# NuPrism_MCPMT_-_ADA4945-1_and_Filter_-_R.net
KiCad netlist of a schematic drawn in Altium Designer
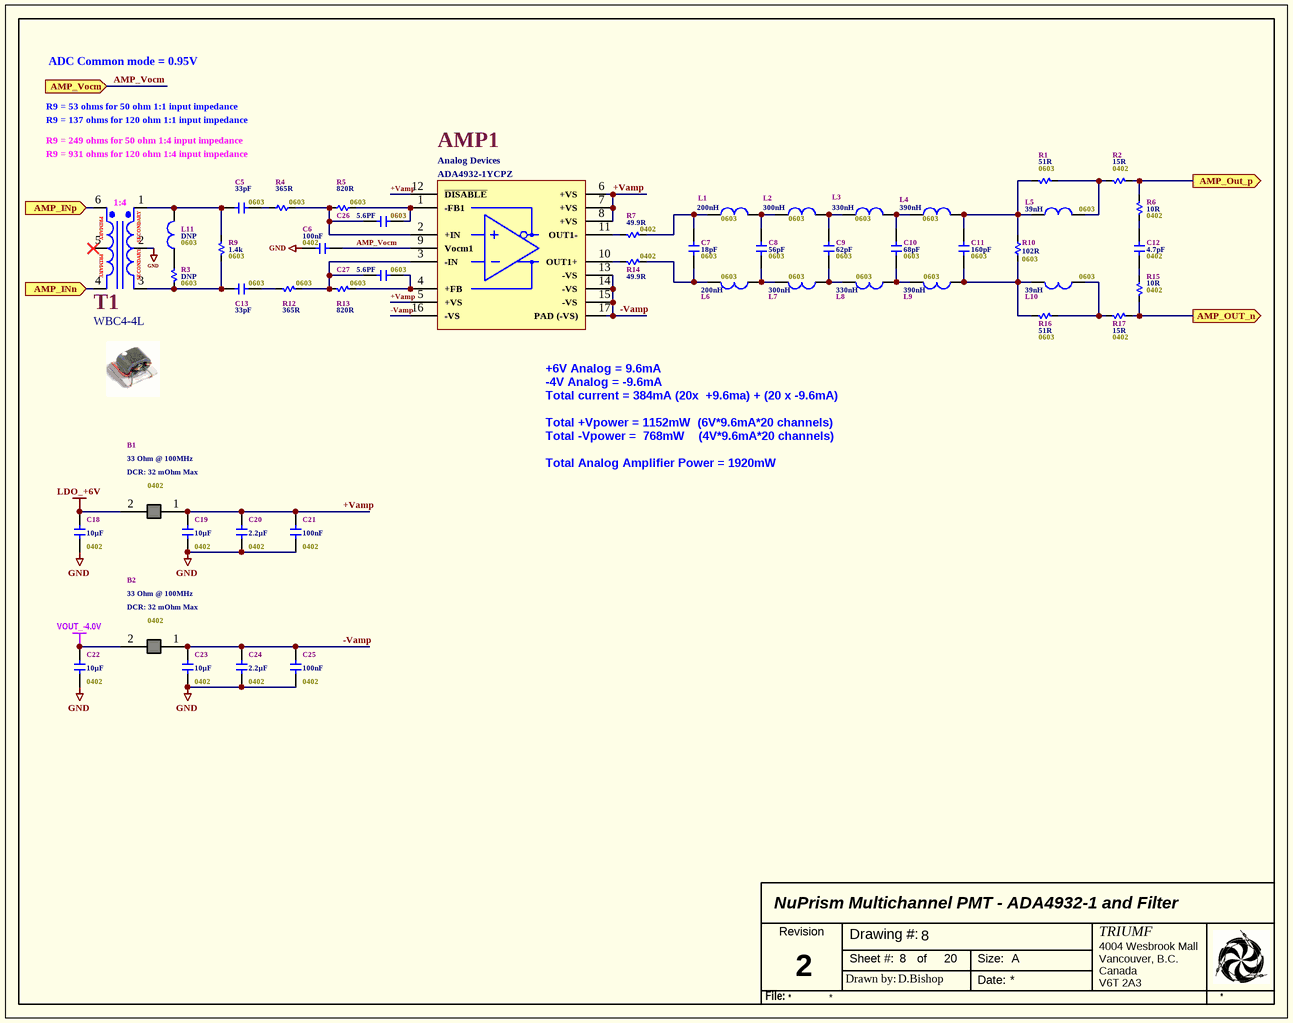
[diagram p0: NuPrism_MCPMT - ADA4945-1 and Filter - Rev2.SchDoc]

(export (version "E")
  (design (tool "Eeschema 10.0.6"))
  (components
    (comp (ref "AMP1")
      (value "ADA4932-1YCPZ")
      (footprint "QFN50P300X300X100-16N_ALT")
      (description "High Speed, ±0.1 µV/˚C Offset Drift, Fully Differential ADC Driver")
      (fields (field (name "MANUFACTURER") "Analog Devices") (field (name "PARTNO") "ADA4932-1YCPZ"))
      (libsource (lib "NuPrism_MCPMT") (part "ADA4932-1YCPZ_ALT"))
    )
    (comp (ref "B1")
      (value "BLM15PX600SN1D")
      (footprint "0402")
      (description "60 Ohms @ 100MHz Ferrite Bead 0402 2.5A")
      (fields
        (field (name "MANUFACTURER") "Murata")
        (field (name "DCR") "32 mOhm Max")
        (field (name "IMPEDANCE @ FREQUENCY") "33 Ohm @ 100MHz")
        (field (name "PACKAGE") "0402")
      )
      (libsource (lib "Clock Distribution Module") (part "Ferrite Bead"))
    )
    (comp (ref "B2")
      (value "BLM15PX600SN1D")
      (footprint "0402")
      (description "60 Ohms @ 100MHz Ferrite Bead 0402 2.5A")
      (fields
        (field (name "MANUFACTURER") "Murata")
        (field (name "DCR") "32 mOhm Max")
        (field (name "IMPEDANCE @ FREQUENCY") "33 Ohm @ 100MHz")
        (field (name "PACKAGE") "0402")
      )
      (libsource (lib "Clock Distribution Module") (part "Ferrite Bead"))
    )
    (comp (ref "C5")
      (value "C0603C330J1GAC7867")
      (footprint "0603")
      (description "33 pF ±5% 100V Ceramic Capacitor C0G, NP0 0603")
      (fields
        (field (name "MANUFACTURER") "KEMET")
        (field (name "CAPACITANCE") "33pF")
        (field (name "PACKAGE") "0603")
        (field (name "VOLTAGE") "100V")
      )
      (libsource (lib "altium-import") (part "root_1_CAP-SMALL_"))
    )
    (comp (ref "C6")
      (value "C0402C104K4RACTU")
      (footprint "0402")
      (description "SMD/SMT 0402 16V 0.1uF X7R 10%")
      (fields
        (field (name "MANUFACTURER") "Kemet")
        (field (name "CAPACITANCE") "100nF")
        (field (name "PACKAGE") "0402")
        (field (name "VOLTAGE") "16V")
      )
      (libsource (lib "NuPrism_MCPMT") (part "CAP-SMALL"))
    )
    (comp (ref "C7")
      (value "CC0603JPNPO9BN180")
      (footprint "0603")
      (description "18 pF ±5% 50V Ceramic Capacitor C0G, NP0 0603")
      (fields
        (field (name "CAPACITANCE") "18pF")
        (field (name "PACKAGE") "0603")
        (field (name "MANUFACTURER") "Yageo")
        (field (name "VOLTAGE") "50V")
      )
      (libsource (lib "altium-import") (part "root_2_CAP-SMALL_"))
    )
    (comp (ref "C8")
      (value "C0603C560J5GAC7867")
      (footprint "0603")
      (description "56 pF ±5% 50V Ceramic Capacitor C0G, NP0 0603 (1608 Metric)")
      (fields
        (field (name "MANUFACTURER") "KEMET")
        (field (name "CAPACITANCE") "56pF")
        (field (name "PACKAGE") "0603")
        (field (name "VOLTAGE") "50V")
      )
      (libsource (lib "altium-import") (part "root_2_CAP-SMALL_"))
    )
    (comp (ref "C9")
      (value "CC0603JRNPO9BN620")
      (footprint "0603")
      (description "62 pF ±5% 50V Ceramic Capacitor C0G, NP0 0603 (1608 Metric)")
      (fields
        (field (name "MANUFACTURER") "YAGEO")
        (field (name "CAPACITANCE") "62pF")
        (field (name "PACKAGE") "0603")
        (field (name "VOLTAGE") "50V")
      )
      (libsource (lib "altium-import") (part "root_2_CAP-SMALL_"))
    )
    (comp (ref "C10")
      (value "CC0603JRNPO9BN680")
      (footprint "0603")
      (description "CAP CER 68PF 50V C0G/NPO 0603 (1608 Metric)")
      (fields
        (field (name "CAPACITANCE") "68pF")
        (field (name "PACKAGE") "0603")
        (field (name "MANUFACTURER") "Yageo")
        (field (name "VOLTAGE") "50V")
      )
      (libsource (lib "altium-import") (part "root_2_CAP-SMALL_"))
    )
    (comp (ref "C11")
      (value "CC0603JRNPO9BN161")
      (footprint "0603")
      (description "160 pF ±5% 50V Ceramic Capacitor C0G, NP0 0603 (1608 Metric)")
      (fields
        (field (name "MANUFACTURER") "YAGEO")
        (field (name "CAPACITANCE") "160pF")
        (field (name "PACKAGE") "0603")
        (field (name "VOLTAGE") "50V")
      )
      (libsource (lib "altium-import") (part "root_2_CAP-SMALL_"))
    )
    (comp (ref "C12")
      (value "CC0402BRNPO9BN4R7")
      (footprint "0402")
      (description "4.7pF ±0.1pF 50V Ceramic Capacitor C0G, NP0 0402")
      (fields
        (field (name "MANUFACTURER") "Yageo")
        (field (name "CAPACITANCE") "4.7pF")
        (field (name "PACKAGE") "0402")
        (field (name "VOLTAGE") "50V")
      )
      (libsource (lib "altium-import") (part "root_2_CAP-SMALL_"))
    )
    (comp (ref "C13")
      (value "C0603C330J1GAC7867")
      (footprint "0603")
      (description "33 pF ±5% 100V Ceramic Capacitor C0G, NP0 0603")
      (fields
        (field (name "MANUFACTURER") "KEMET")
        (field (name "CAPACITANCE") "33pF")
        (field (name "PACKAGE") "0603")
        (field (name "VOLTAGE") "100V")
      )
      (libsource (lib "altium-import") (part "root_3_mirrored_CAP-SMALL_"))
    )
    (comp (ref "C18")
      (value "CL05A106MQ5NRNC")
      (footprint "0402")
      (description "10 µF ±20% 6.3V Ceramic Capacitor X5R 0402 (1005 Metric)")
      (fields
        (field (name "CAPACITANCE") "10µF")
        (field (name "PACKAGE") "0402")
        (field (name "MANUFACTURER") "Samsung Electro-Mechanics")
        (field (name "VOLTAGE") "6.3V")
      )
      (libsource (lib "") (part "root_2_CAP-SMALL__1"))
    )
    (comp (ref "C19")
      (value "CL05A106MQ5NRNC")
      (footprint "0402")
      (description "10 µF ±20% 6.3V Ceramic Capacitor X5R 0402 (1005 Metric)")
      (fields
        (field (name "CAPACITANCE") "10µF")
        (field (name "PACKAGE") "0402")
        (field (name "MANUFACTURER") "Samsung Electro-Mechanics")
        (field (name "VOLTAGE") "6.3V")
      )
      (libsource (lib "") (part "root_2_CAP-SMALL__1"))
    )
    (comp (ref "C20")
      (value "TMK105CBJ225KV-F")
      (footprint "0402")
      (description "SMD/SMT 0402 25V 2.2uF 10% X5R")
      (fields
        (field (name "MANUFACTURER") "Taiyo Yuden")
        (field (name "CAPACITANCE") "2.2µF")
        (field (name "PACKAGE") "0402")
        (field (name "VOLTAGE") "25V")
      )
      (libsource (lib "altium-import") (part "root_0_CAP-SMALL_"))
    )
    (comp (ref "C21")
      (value "C0402C104K4RACTU")
      (footprint "0402")
      (description "SMD/SMT 0402 16V 0.1uF X7R 10%")
      (fields
        (field (name "MANUFACTURER") "Kemet")
        (field (name "CAPACITANCE") "100nF")
        (field (name "PACKAGE") "0402")
        (field (name "VOLTAGE") "16V")
      )
      (libsource (lib "NuPrism_MCPMT") (part "CAP-SMALL"))
    )
    (comp (ref "C22")
      (value "CL05A106MQ5NRNC")
      (footprint "0402")
      (description "10 µF ±20% 6.3V Ceramic Capacitor X5R 0402 (1005 Metric)")
      (fields
        (field (name "CAPACITANCE") "10µF")
        (field (name "PACKAGE") "0402")
        (field (name "MANUFACTURER") "Samsung Electro-Mechanics")
        (field (name "VOLTAGE") "6.3V")
      )
      (libsource (lib "") (part "root_2_CAP-SMALL__1"))
    )
    (comp (ref "C23")
      (value "CL05A106MQ5NRNC")
      (footprint "0402")
      (description "10 µF ±20% 6.3V Ceramic Capacitor X5R 0402 (1005 Metric)")
      (fields
        (field (name "CAPACITANCE") "10µF")
        (field (name "PACKAGE") "0402")
        (field (name "MANUFACTURER") "Samsung Electro-Mechanics")
        (field (name "VOLTAGE") "6.3V")
      )
      (libsource (lib "") (part "root_2_CAP-SMALL__1"))
    )
    (comp (ref "C24")
      (value "TMK105CBJ225KV-F")
      (footprint "0402")
      (description "SMD/SMT 0402 25V 2.2uF 10% X5R")
      (fields
        (field (name "MANUFACTURER") "Taiyo Yuden")
        (field (name "CAPACITANCE") "2.2µF")
        (field (name "PACKAGE") "0402")
        (field (name "VOLTAGE") "25V")
      )
      (libsource (lib "altium-import") (part "root_0_CAP-SMALL_"))
    )
    (comp (ref "C25")
      (value "C0402C104K4RACTU")
      (footprint "0402")
      (description "SMD/SMT 0402 16V 0.1uF X7R 10%")
      (fields
        (field (name "MANUFACTURER") "Kemet")
        (field (name "CAPACITANCE") "100nF")
        (field (name "PACKAGE") "0402")
        (field (name "VOLTAGE") "16V")
      )
      (libsource (lib "NuPrism_MCPMT") (part "CAP-SMALL"))
    )
    (comp (ref "C26")
      (value "06035A5R6JAT2A")
      (footprint "0603")
      (description "5.6 pF ±5% 50V Ceramic Capacitor C0G, NP0 0603")
      (fields
        (field (name "MANUFACTURER") "KYOCERA AVX")
        (field (name "CAPACITANCE") "5.6PF")
        (field (name "PACKAGE") "0603")
        (field (name "VOLTAGE") "50V")
      )
      (libsource (lib "altium-import") (part "root_3_CAP-SMALL_"))
    )
    (comp (ref "C27")
      (value "06035A5R6JAT2A")
      (footprint "0603")
      (description "5.6 pF ±5% 50V Ceramic Capacitor C0G, NP0 0603")
      (fields
        (field (name "MANUFACTURER") "KYOCERA AVX")
        (field (name "CAPACITANCE") "5.6PF")
        (field (name "PACKAGE") "0603")
        (field (name "VOLTAGE") "50V")
      )
      (libsource (lib "altium-import") (part "root_3_CAP-SMALL_"))
    )
    (comp (ref "L1")
      (value "LQW18ANR20J8ZD")
      (footprint "NumPrism Mutichannel PMT:0603 - Inductor")
      (description "200 nH Unshielded Wirewound Inductor 120 mA 2.40Ohm Max 0603")
      (fields
        (field (name "PACKAGE") "0603")
        (field (name "INDUCTANCE") "200nH")
        (field (name "MANUFACTURER") "Murata Electronics")
        (field (name "PARTNO") "LQW18ANR20G00D")
      )
      (libsource (lib "NuPrism - mPMT") (part "Inductor1"))
    )
    (comp (ref "L2")
      (value "LQW18ANR30G80D")
      (footprint "0603 - Inductor")
      (description "300 nH Unshielded Wirewound Inductor 220 mA 3.12Ohm Max 0603")
      (fields
        (field (name "PACKAGE") "0603")
        (field (name "INDUCTANCE") "300nH")
        (field (name "MANUFACTURER") "Coilcraft")
        (field (name "PARTNO") "LQW18ANR30G8ZD")
      )
      (libsource (lib "NuPrism - mPMT") (part "Inductor1"))
    )
    (comp (ref "L3")
      (value "LQW18CNR33J00D")
      (footprint "0603 - Inductor")
      (description "330 nH Unshielded Drum Core, Wirewound Inductor 630 mA 250mOhm Max 0603")
      (fields
        (field (name "PACKAGE") "0603")
        (field (name "INDUCTANCE") "330nH")
        (field (name "MANUFACTURER") "Murata Electronics")
      )
      (libsource (lib "NuPrism - mPMT") (part "Inductor1"))
    )
    (comp (ref "L4")
      (value "MLJ1608WR39JT000")
      (footprint "0603 - inductor")
      (description "390 nH Shielded Multilayer Inductor 450 mA 364mOhm Max 0603 (1608 Metric)")
      (fields
        (field (name "PACKAGE") "0603")
        (field (name "INDUCTANCE") "390nH")
        (field (name "MANUFACTURER") "TDK Corporation")
      )
      (libsource (lib "NuPrism - mPMT") (part "Inductor1"))
    )
    (comp (ref "L5")
      (value "LQW18AN39NJ00D")
      (footprint "0603 - Inductor_2")
      (description "39 nH Unshielded Wirewound Inductor 400 mA 260mOhm Max 0603 (1608 Metric)")
      (fields
        (field (name "PACKAGE") "0603")
        (field (name "INDUCTANCE") "39nH")
        (field (name "MANUFACTURER") "Murata Electronics")
      )
      (libsource (lib "NuPrism - mPMT") (part "Inductor1"))
    )
    (comp (ref "L6")
      (value "LQW18ANR20J8ZD")
      (footprint "0603 - Inductor")
      (description "200 nH Unshielded Wirewound Inductor 120 mA 2.40Ohm Max 0603")
      (fields
        (field (name "PACKAGE") "0603")
        (field (name "INDUCTANCE") "200nH")
        (field (name "MANUFACTURER") "Murata Electronics")
        (field (name "PARTNO") "LQW18ANR20G00D")
      )
      (libsource (lib "") (part "Inductor1_1"))
    )
    (comp (ref "L7")
      (value "LQW18ANR30G80D")
      (footprint "0603 - Inductor")
      (description "300 nH Unshielded Wirewound Inductor 220 mA 3.12Ohm Max 0603")
      (fields
        (field (name "PACKAGE") "0603")
        (field (name "INDUCTANCE") "300nH")
        (field (name "MANUFACTURER") "Coilcraft")
        (field (name "PARTNO") "LQW18ANR30G8ZD")
      )
      (libsource (lib "") (part "Inductor1_1"))
    )
    (comp (ref "L8")
      (value "LQW18CNR33J00D")
      (footprint "0603 - Inductor")
      (description "330 nH Unshielded Drum Core, Wirewound Inductor 630 mA 250mOhm Max 0603")
      (fields
        (field (name "PACKAGE") "0603")
        (field (name "INDUCTANCE") "330nH")
        (field (name "MANUFACTURER") "Murata Electronics")
      )
      (libsource (lib "") (part "Inductor1_1"))
    )
    (comp (ref "L9")
      (value "MLJ1608WR39JT000")
      (footprint "0603 - inductor")
      (description "390 nH Shielded Multilayer Inductor 450 mA 364mOhm Max 0603 (1608 Metric)")
      (fields
        (field (name "PACKAGE") "0603")
        (field (name "INDUCTANCE") "390nH")
        (field (name "MANUFACTURER") "TDK Corporation")
      )
      (libsource (lib "") (part "Inductor1_1"))
    )
    (comp (ref "L10")
      (value "LQW18AN39NJ00D")
      (footprint "0603 - Inductor_2")
      (description "39 nH Unshielded Wirewound Inductor 400 mA 260mOhm Max 0603 (1608 Metric)")
      (fields
        (field (name "PACKAGE") "0603")
        (field (name "INDUCTANCE") "39nH")
        (field (name "MANUFACTURER") "Murata Electronics")
      )
      (libsource (lib "") (part "Inductor1_1"))
    )
    (comp (ref "L11")
      (value "~")
      (footprint "0603 - Inductor")
      (description "Do not put")
      (fields (field (name "PACKAGE") "0603") (field (name "INDUCTANCE") "DNP"))
      (libsource (lib "NuPrism - mPMT") (part "Inductor1"))
    )
    (comp (ref "R1")
      (value "RC0603FR-0751RL")
      (footprint "0603")
      (description "Thick Film Resistors - SMD 51 OHM 1%")
      (fields
        (field (name "MANUFACTURER") "Yageo")
        (field (name "RESISTANCE") "51R")
        (field (name "PACKAGE") "0603")
      )
      (libsource (lib "NuPrism - mPMT") (part "RES-TINY"))
    )
    (comp (ref "R2")
      (value "RMCF0402FT15R0")
      (footprint "0402")
      (description "15 Ohms ±1% 0.063W, 1/16W Chip Resistor 0402 (1005 Metric)")
      (fields
        (field (name "MANUFACTURER") "Stackpole Electronics Inc")
        (field (name "RESISTANCE") "15R")
        (field (name "PACKAGE") "0402")
      )
      (libsource (lib "NuPrism - mPMT") (part "RES-TINY"))
    )
    (comp (ref "R3")
      (value "~")
      (footprint "0603")
      (description "Do not put")
      (fields
        (field (name "MANUFACTURER") "Yageo")
        (field (name "PARTNO") "RT0603BRD07820RL")
        (field (name "RESISTANCE") "DNP")
        (field (name "PACKAGE") "0603")
      )
      (libsource (lib "NuPrism - mPMT") (part "RES-TINY"))
    )
    (comp (ref "R4")
      (value "ERJ-PB3B3650V")
      (footprint "0603")
      (description "Thick Film Resistors - SMD 0603 Anti-Surge Res. 0.1%, 365ohm")
      (fields
        (field (name "MANUFACTURER") "Panasonic")
        (field (name "RESISTANCE") "365R")
        (field (name "PACKAGE") "0603")
      )
      (libsource (lib "NuPrism - mPMT") (part "RES-TINY"))
    )
    (comp (ref "R5")
      (value "RT0603BRD07820RL")
      (footprint "0603")
      (description "820 Ohms ±0.1% 0.1W, 1/10W Chip Resistor 0603 (1608 Metric) Thin Film")
      (fields
        (field (name "MANUFACTURER") "Yageo")
        (field (name "RESISTANCE") "820R")
        (field (name "PACKAGE") "0603")
      )
      (libsource (lib "NuPrism - mPMT") (part "RES-TINY"))
    )
    (comp (ref "R6")
      (value "RC0402FR-0710RL")
      (footprint "0402")
      (description "10 Ohms ±1% 0.063W, 1/16W Chip Resistor 0402")
      (fields
        (field (name "MANUFACTURER") "Yageo")
        (field (name "RESISTANCE") "10R")
        (field (name "PACKAGE") "0402")
        (field (name "VOLTAGE") "50V")
      )
      (libsource (lib "") (part "RES-TINY_2"))
    )
    (comp (ref "R7")
      (value "RMCF0402FT49R9")
      (footprint "0402")
      (description "49.9 Ohms ±1% 0.063W, 1/16W Chip Resistor 0402 (1005 Metric)")
      (fields
        (field (name "MANUFACTURER") "Stackpole Electronics Inc")
        (field (name "RESISTANCE") "49.9R")
        (field (name "PACKAGE") "0402")
      )
      (libsource (lib "NuPrism - mPMT") (part "RES-TINY"))
    )
    (comp (ref "R9")
      (value "RC0603FR-101K4L")
      (footprint "0603")
      (description "1.4 kOhms ±1% 0.1W, 1/10W Chip Resistor 0603 (1608 Metric) Thick Film")
      (fields
        (field (name "MANUFACTURER") "Stackpole")
        (field (name "PARTNO") "RC0603FR-101K2L")
        (field (name "RESISTANCE") "1.4k")
        (field (name "PACKAGE") "0603")
      )
      (libsource (lib "NuPrism - mPMT") (part "RES-TINY"))
    )
    (comp (ref "R10")
      (value "RC0603FR-07102RL")
      (footprint "0603")
      (description "102 Ohms ±1% 0.1W, 1/10W Chip Resistor 0603")
      (fields
        (field (name "MANUFACTURER") "Yageo")
        (field (name "RESISTANCE") "102R")
        (field (name "PACKAGE") "0603")
      )
      (libsource (lib "NuPrism - mPMT") (part "RES-TINY"))
    )
    (comp (ref "R12")
      (value "ERJ-PB3B3650V")
      (footprint "0603")
      (description "Thick Film Resistors - SMD 0603 Anti-Surge Res. 0.1%, 365ohm")
      (fields
        (field (name "MANUFACTURER") "Panasonic")
        (field (name "RESISTANCE") "365R")
        (field (name "PACKAGE") "0603")
      )
      (libsource (lib "NuPrism - mPMT") (part "RES-TINY"))
    )
    (comp (ref "R13")
      (value "RT0603BRD07820RL")
      (footprint "0603")
      (description "820 Ohms ±0.1% 0.1W, 1/10W Chip Resistor 0603 (1608 Metric) Thin Film")
      (fields
        (field (name "MANUFACTURER") "Yageo")
        (field (name "RESISTANCE") "820R")
        (field (name "PACKAGE") "0603")
      )
      (libsource (lib "NuPrism - mPMT") (part "RES-TINY"))
    )
    (comp (ref "R14")
      (value "RMCF0402FT49R9")
      (footprint "0402")
      (description "49.9 Ohms ±1% 0.063W, 1/16W Chip Resistor 0402 (1005 Metric)")
      (fields
        (field (name "MANUFACTURER") "Stackpole Electronics Inc")
        (field (name "RESISTANCE") "49.9R")
        (field (name "PACKAGE") "0402")
      )
      (libsource (lib "NuPrism - mPMT") (part "RES-TINY"))
    )
    (comp (ref "R15")
      (value "RC0402FR-0710RL")
      (footprint "0402")
      (description "10 Ohms ±1% 0.063W, 1/16W Chip Resistor 0402")
      (fields
        (field (name "MANUFACTURER") "Yageo")
        (field (name "RESISTANCE") "10R")
        (field (name "PACKAGE") "0402")
        (field (name "VOLTAGE") "50V")
      )
      (libsource (lib "") (part "RES-TINY_1"))
    )
    (comp (ref "R16")
      (value "RC0603FR-0751RL")
      (footprint "0603")
      (description "Thick Film Resistors - SMD 51 OHM 1%")
      (fields
        (field (name "MANUFACTURER") "Yageo")
        (field (name "RESISTANCE") "51R")
        (field (name "PACKAGE") "0603")
      )
      (libsource (lib "NuPrism - mPMT") (part "RES-TINY"))
    )
    (comp (ref "R17")
      (value "RMCF0402FT15R0")
      (footprint "0402")
      (description "15 Ohms ±1% 0.063W, 1/16W Chip Resistor 0402 (1005 Metric)")
      (fields
        (field (name "MANUFACTURER") "Stackpole Electronics Inc")
        (field (name "RESISTANCE") "15R")
        (field (name "PACKAGE") "0402")
      )
      (libsource (lib "NuPrism - mPMT") (part "RES-TINY"))
    )
    (comp (ref "T1")
      (value "WBC4-4L")
      (footprint "WBC4-4WL")
      (description "Audio Transformers / Signal Transformers WBC SMT Mini Wdebnd 1:4 0.250-800 MHz")
      (fields (field (name "MANUFACTURER") "Coilcraft"))
      (libsource (lib "NuPrism_MCPMT") (part "WBC4-4L"))
    )
  )
  (nets
    (net (code "1") (name "/+Vamp") (class "Default")
      (node (ref "AMP1") (pin "12") (pinfunction "~{DISABLE}_12") (pintype "passive"))
      (node (ref "AMP1") (pin "5") (pinfunction "+VS_5") (pintype "power_in"))
      (node (ref "AMP1") (pin "6") (pinfunction "+VS_6") (pintype "power_in"))
      (node (ref "AMP1") (pin "7") (pinfunction "+VS_7") (pintype "power_in"))
      (node (ref "AMP1") (pin "8") (pinfunction "+VS_8") (pintype "power_in"))
      (node (ref "B1") (pin "1") (pinfunction "1_1") (pintype "passive"))
      (node (ref "C19") (pin "2") (pintype "passive"))
      (node (ref "C20") (pin "1") (pintype "passive"))
      (node (ref "C21") (pin "1") (pintype "passive"))
    )
    (net (code "2") (name "/-Vamp") (class "Default")
      (node (ref "AMP1") (pin "13") (pinfunction "-VS_13") (pintype "power_in"))
      (node (ref "AMP1") (pin "14") (pinfunction "-VS_14") (pintype "power_in"))
      (node (ref "AMP1") (pin "15") (pinfunction "-VS_15") (pintype "power_in"))
      (node (ref "AMP1") (pin "16") (pinfunction "-VS_16") (pintype "power_in"))
      (node (ref "AMP1") (pin "17") (pinfunction "PAD_(-VS)_17") (pintype "power_in"))
      (node (ref "B2") (pin "1") (pinfunction "1_1") (pintype "passive"))
      (node (ref "C23") (pin "2") (pintype "passive"))
      (node (ref "C24") (pin "1") (pintype "passive"))
      (node (ref "C25") (pin "1") (pintype "passive"))
    )
    (net (code "3") (name "/AMP_INn") (class "Default")
      (node (ref "T1") (pin "4") (pinfunction "Pri-_4") (pintype "passive"))
    )
    (net (code "4") (name "/AMP_INp") (class "Default")
      (node (ref "T1") (pin "6") (pinfunction "Pri+_6") (pintype "passive"))
    )
    (net (code "5") (name "/AMP_OUT_n") (class "Default")
      (node (ref "R15") (pin "1") (pintype "output"))
      (node (ref "R17") (pin "2") (pintype "passive"))
    )
    (net (code "6") (name "/AMP_Out_p") (class "Default")
      (node (ref "R2") (pin "2") (pintype "passive"))
      (node (ref "R6") (pin "2") (pintype "output"))
    )
    (net (code "7") (name "/AMP_Vocm") (class "Default")
      (node (ref "AMP1") (pin "9") (pinfunction "Vocm1_9") (pintype "passive"))
      (node (ref "C6") (pin "2") (pintype "passive"))
    )
    (net (code "8") (name "GND") (class "Default")
      (node (ref "C18") (pin "1") (pintype "passive"))
      (node (ref "C19") (pin "1") (pintype "passive"))
      (node (ref "C20") (pin "2") (pintype "passive"))
      (node (ref "C21") (pin "2") (pintype "passive"))
      (node (ref "C22") (pin "1") (pintype "passive"))
      (node (ref "C23") (pin "1") (pintype "passive"))
      (node (ref "C24") (pin "2") (pintype "passive"))
      (node (ref "C25") (pin "2") (pintype "passive"))
      (node (ref "C6") (pin "1") (pintype "passive"))
      (node (ref "T1") (pin "2") (pinfunction "SecCT_2") (pintype "passive"))
    )
    (net (code "9") (name "LDO_+6V") (class "Default")
      (node (ref "B1") (pin "2") (pinfunction "2_2") (pintype "passive"))
      (node (ref "C18") (pin "2") (pintype "passive"))
    )
    (net (code "10") (name "Net-(AMP1-+FB)") (class "Default")
      (node (ref "AMP1") (pin "4") (pinfunction "+FB_4") (pintype "passive"))
      (node (ref "C27") (pin "1") (pintype "passive"))
      (node (ref "R13") (pin "1") (pintype "passive"))
    )
    (net (code "11") (name "Net-(AMP1-+IN)") (class "Default")
      (node (ref "AMP1") (pin "2") (pinfunction "+IN_2") (pintype "passive"))
      (node (ref "C26") (pin "2") (pintype "passive"))
      (node (ref "R4") (pin "1") (pintype "passive"))
      (node (ref "R5") (pin "2") (pintype "passive"))
    )
    (net (code "12") (name "Net-(AMP1--FB1)") (class "Default")
      (node (ref "AMP1") (pin "1") (pinfunction "-FB1_1") (pintype "passive"))
      (node (ref "C26") (pin "1") (pintype "passive"))
      (node (ref "R5") (pin "1") (pintype "passive"))
    )
    (net (code "13") (name "Net-(AMP1--IN)") (class "Default")
      (node (ref "AMP1") (pin "3") (pinfunction "-IN_3") (pintype "passive"))
      (node (ref "C27") (pin "2") (pintype "passive"))
      (node (ref "R12") (pin "1") (pintype "passive"))
      (node (ref "R13") (pin "2") (pintype "passive"))
    )
    (net (code "14") (name "Net-(AMP1-OUT1+)") (class "Default")
      (node (ref "AMP1") (pin "10") (pinfunction "OUT1+_10") (pintype "passive"))
      (node (ref "R14") (pin "2") (pintype "passive"))
    )
    (net (code "15") (name "Net-(AMP1-OUT1-)") (class "Default")
      (node (ref "AMP1") (pin "11") (pinfunction "OUT1-_11") (pintype "passive"))
      (node (ref "R7") (pin "2") (pintype "passive"))
    )
    (net (code "16") (name "Net-(C5-Pad2)") (class "Default")
      (node (ref "C5") (pin "2") (pintype "passive"))
      (node (ref "R4") (pin "2") (pintype "passive"))
    )
    (net (code "17") (name "Net-(C7-Pad1)") (class "Default")
      (node (ref "C7") (pin "1") (pintype "passive"))
      (node (ref "L6") (pin "1") (pinfunction "1_1") (pintype "passive"))
      (node (ref "R14") (pin "1") (pintype "passive"))
    )
    (net (code "18") (name "Net-(C7-Pad2)") (class "Default")
      (node (ref "C7") (pin "2") (pintype "passive"))
      (node (ref "L1") (pin "1") (pinfunction "1_1") (pintype "passive"))
      (node (ref "R7") (pin "1") (pintype "passive"))
    )
    (net (code "19") (name "Net-(C8-Pad1)") (class "Default")
      (node (ref "C8") (pin "1") (pintype "passive"))
      (node (ref "L6") (pin "2") (pinfunction "2_2") (pintype "passive"))
      (node (ref "L7") (pin "1") (pinfunction "1_1") (pintype "passive"))
    )
    (net (code "20") (name "Net-(C8-Pad2)") (class "Default")
      (node (ref "C8") (pin "2") (pintype "passive"))
      (node (ref "L1") (pin "2") (pinfunction "2_2") (pintype "passive"))
      (node (ref "L2") (pin "1") (pinfunction "1_1") (pintype "passive"))
    )
    (net (code "21") (name "Net-(C9-Pad1)") (class "Default")
      (node (ref "C9") (pin "1") (pintype "passive"))
      (node (ref "L7") (pin "2") (pinfunction "2_2") (pintype "passive"))
      (node (ref "L8") (pin "1") (pinfunction "1_1") (pintype "passive"))
    )
    (net (code "22") (name "Net-(C9-Pad2)") (class "Default")
      (node (ref "C9") (pin "2") (pintype "passive"))
      (node (ref "L2") (pin "2") (pinfunction "2_2") (pintype "passive"))
      (node (ref "L3") (pin "1") (pinfunction "1_1") (pintype "passive"))
    )
    (net (code "23") (name "Net-(C10-Pad1)") (class "Default")
      (node (ref "C10") (pin "1") (pintype "passive"))
      (node (ref "L8") (pin "2") (pinfunction "2_2") (pintype "passive"))
      (node (ref "L9") (pin "1") (pinfunction "1_1") (pintype "passive"))
    )
    (net (code "24") (name "Net-(C10-Pad2)") (class "Default")
      (node (ref "C10") (pin "2") (pintype "passive"))
      (node (ref "L3") (pin "2") (pinfunction "2_2") (pintype "passive"))
      (node (ref "L4") (pin "1") (pinfunction "1_1") (pintype "passive"))
    )
    (net (code "25") (name "Net-(C11-Pad1)") (class "Default")
      (node (ref "C11") (pin "1") (pintype "passive"))
      (node (ref "L10") (pin "1") (pinfunction "1_1") (pintype "passive"))
      (node (ref "L9") (pin "2") (pinfunction "2_2") (pintype "passive"))
      (node (ref "R10") (pin "2") (pintype "passive"))
      (node (ref "R16") (pin "1") (pintype "passive"))
    )
    (net (code "26") (name "Net-(C11-Pad2)") (class "Default")
      (node (ref "C11") (pin "2") (pintype "passive"))
      (node (ref "L4") (pin "2") (pinfunction "2_2") (pintype "passive"))
      (node (ref "L5") (pin "1") (pinfunction "1_1") (pintype "passive"))
      (node (ref "R1") (pin "1") (pintype "passive"))
      (node (ref "R10") (pin "1") (pintype "passive"))
    )
    (net (code "27") (name "Net-(C12-Pad1)") (class "Default")
      (node (ref "C12") (pin "1") (pintype "passive"))
      (node (ref "R15") (pin "2") (pintype "passive"))
    )
    (net (code "28") (name "Net-(C12-Pad2)") (class "Default")
      (node (ref "C12") (pin "2") (pintype "passive"))
      (node (ref "R6") (pin "1") (pintype "passive"))
    )
    (net (code "29") (name "Net-(C13-Pad2)") (class "Default")
      (node (ref "C13") (pin "2") (pintype "passive"))
      (node (ref "R12") (pin "2") (pintype "passive"))
    )
    (net (code "30") (name "Net-(L5-Pad2)") (class "Default")
      (node (ref "L5") (pin "2") (pinfunction "2_2") (pintype "passive"))
      (node (ref "R1") (pin "2") (pintype "passive"))
      (node (ref "R2") (pin "1") (pintype "passive"))
    )
    (net (code "31") (name "Net-(L10-Pad2)") (class "Default")
      (node (ref "L10") (pin "2") (pinfunction "2_2") (pintype "passive"))
      (node (ref "R16") (pin "2") (pintype "passive"))
      (node (ref "R17") (pin "1") (pintype "passive"))
    )
    (net (code "32") (name "Net-(L11-Pad1)") (class "Default")
      (node (ref "L11") (pin "1") (pinfunction "1_1") (pintype "passive"))
      (node (ref "R3") (pin "1") (pintype "passive"))
    )
    (net (code "33") (name "Net-(T1-Sec+)") (class "Default")
      (node (ref "C5") (pin "1") (pintype "passive"))
      (node (ref "L11") (pin "2") (pinfunction "2_2") (pintype "passive"))
      (node (ref "R9") (pin "1") (pintype "passive"))
      (node (ref "T1") (pin "1") (pinfunction "Sec+_1") (pintype "passive"))
    )
    (net (code "34") (name "Net-(T1-Sec-)") (class "Default")
      (node (ref "C13") (pin "1") (pintype "passive"))
      (node (ref "R3") (pin "2") (pintype "passive"))
      (node (ref "R9") (pin "2") (pintype "passive"))
      (node (ref "T1") (pin "3") (pinfunction "Sec-_3") (pintype "passive"))
    )
    (net (code "35") (name "VOUT_-4.0V") (class "Default")
      (node (ref "B2") (pin "2") (pinfunction "2_2") (pintype "passive"))
      (node (ref "C22") (pin "2") (pintype "passive"))
    )
    (net (code "36") (name "unconnected-(T1-PriCT-Pad5)") (class "Default")
      (node (ref "T1") (pin "5") (pinfunction "PriCT_5") (pintype "passive+no_connect"))
    )
  )
)
